# SCH_NFC-Card_2024-10-23.net
KiCad netlist of a schematic drawn in EasyEDA
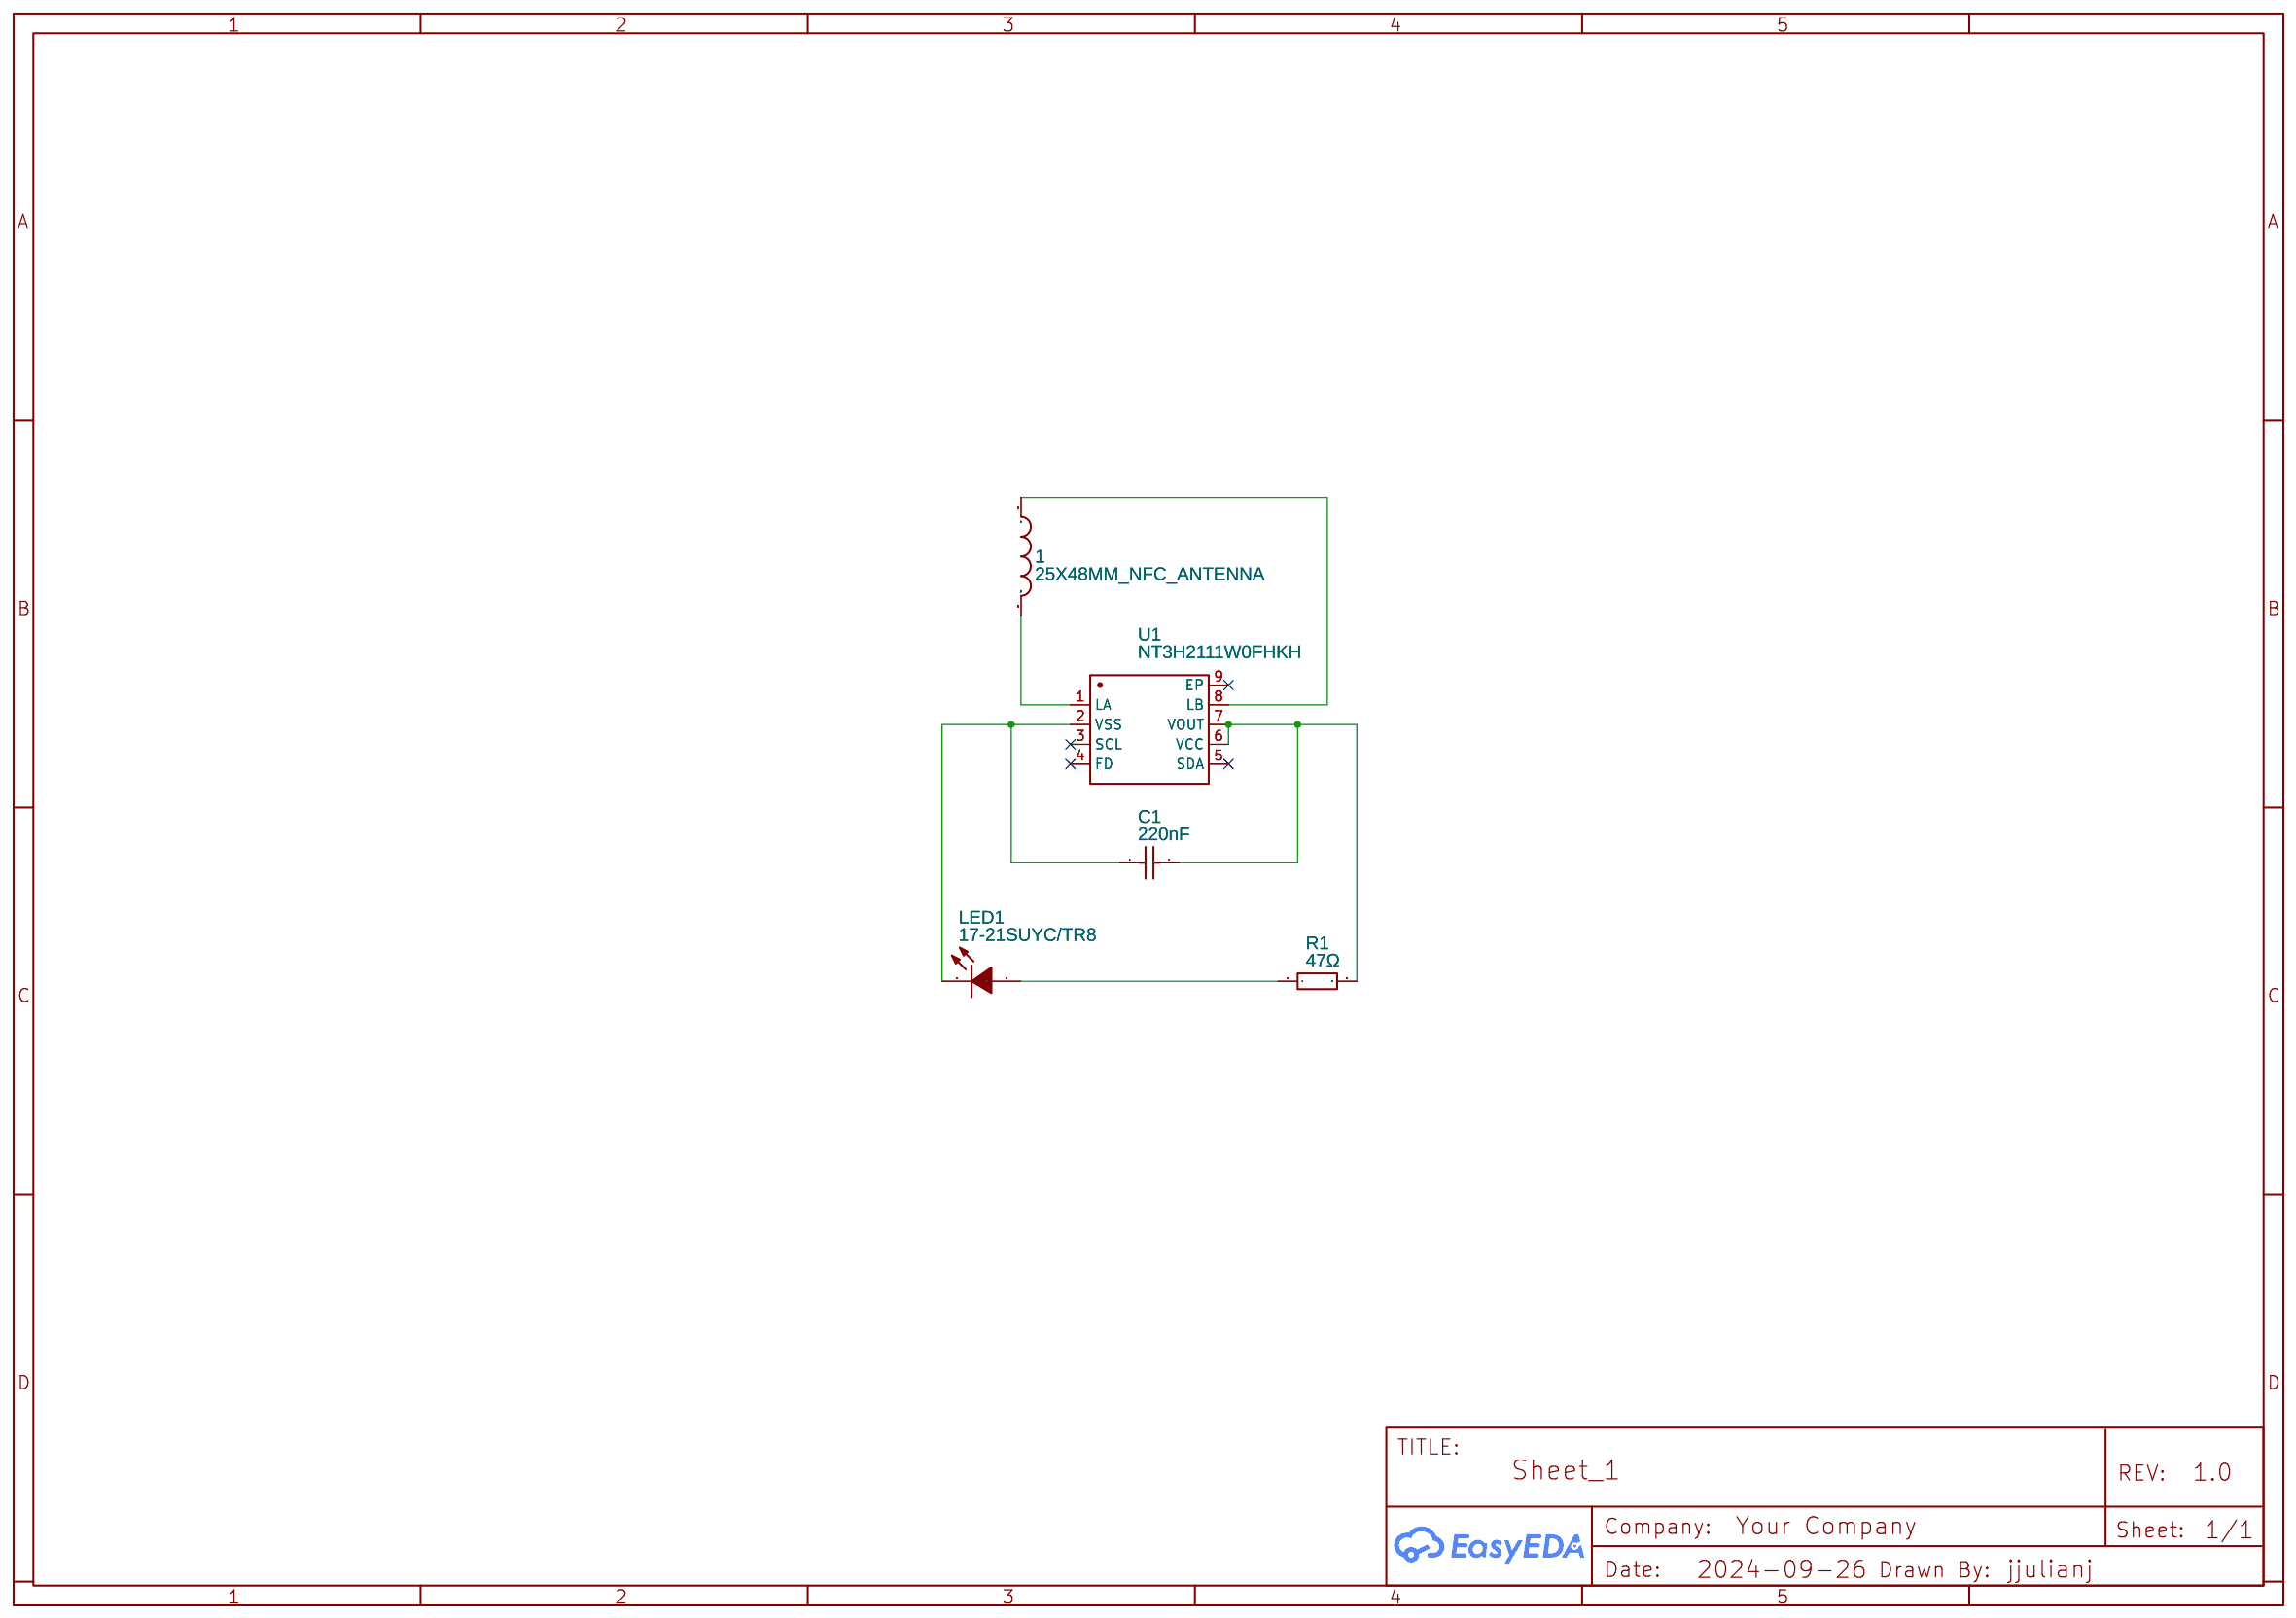
[diagram p0: schematic sheet]

(export (version "E")
  (design (tool "Eeschema 10.0.6"))
  (components
    (comp (ref "1") (value "25X48MM_NFC_ANTENNA") (libsource (lib "") (part "25X48MM_NFC_ANTENNA")))
    (comp (ref "C1")
      (value "220nF")
      (fields
        (field (name "Manufacturer Part") "CL10B224KA8NNNC")
        (field (name "Manufacturer") "SAMSUNG(三星)")
      )
      (libsource (lib "") (part "CL10B224KA8NNNC"))
    )
    (comp (ref "LED1")
      (value "17-21SUYC/TR8")
      (fields (field (name "Manufacturer Part") "KT-0805黄灯") (field (name "Manufacturer") "KENTO"))
      (libsource (lib "") (part "17-21SUYC/TR8"))
    )
    (comp (ref "R1")
      (value "47Ω")
      (fields
        (field (name "Manufacturer Part") "0603WAF470JT5E")
        (field (name "Manufacturer") "UNI-ROYAL(厚声)")
      )
      (libsource (lib "") (part "0603WAF470JT5E"))
    )
    (comp (ref "U1")
      (value "NT3H2111W0FHKH")
      (fields (field (name "Manufacturer") "NXP(恩智浦)"))
      (libsource (lib "") (part "NT3H2111W0FHKH"))
    )
  )
  (nets
    (net (code "1") (name "Net-(LED1-+)") (class "Default")
      (node (ref "LED1") (pin "1") (pinfunction "+_1") (pintype "unspecified"))
      (node (ref "R1") (pin "1") (pinfunction "1_1") (pintype "input"))
    )
    (net (code "2") (name "Net-(LED1--)") (class "Default")
      (node (ref "C1") (pin "1") (pinfunction "1_1") (pintype "input"))
      (node (ref "LED1") (pin "2") (pinfunction "-_2") (pintype "unspecified"))
      (node (ref "U1") (pin "2") (pinfunction "VSS_2") (pintype "unspecified"))
    )
    (net (code "3") (name "Net-(U1-LA)") (class "Default")
      (node (ref "1") (pin "P$2") (pinfunction "P$2_P$2") (pintype "bidirectional"))
      (node (ref "U1") (pin "1") (pinfunction "LA_1") (pintype "unspecified"))
    )
    (net (code "4") (name "Net-(U1-LB)") (class "Default")
      (node (ref "1") (pin "P$1") (pinfunction "P$1_P$1") (pintype "bidirectional"))
      (node (ref "U1") (pin "8") (pinfunction "LB_8") (pintype "unspecified"))
    )
    (net (code "5") (name "Net-(U1-VCC)") (class "Default")
      (node (ref "C1") (pin "2") (pinfunction "2_2") (pintype "input"))
      (node (ref "R1") (pin "2") (pinfunction "2_2") (pintype "input"))
      (node (ref "U1") (pin "6") (pinfunction "VCC_6") (pintype "unspecified"))
      (node (ref "U1") (pin "7") (pinfunction "VOUT_7") (pintype "unspecified"))
    )
    (net (code "6") (name "unconnected-(U1-EP-Pad9)") (class "Default")
      (node (ref "U1") (pin "9") (pinfunction "EP_9") (pintype "unspecified+no_connect"))
    )
    (net (code "7") (name "unconnected-(U1-FD-Pad4)") (class "Default")
      (node (ref "U1") (pin "4") (pinfunction "FD_4") (pintype "unspecified+no_connect"))
    )
    (net (code "8") (name "unconnected-(U1-SCL-Pad3)") (class "Default")
      (node (ref "U1") (pin "3") (pinfunction "SCL_3") (pintype "unspecified+no_connect"))
    )
    (net (code "9") (name "unconnected-(U1-SDA-Pad5)") (class "Default")
      (node (ref "U1") (pin "5") (pinfunction "SDA_5") (pintype "unspecified+no_connect"))
    )
  )
)
